# sch.net
KiCad netlist of a schematic drawn in EAGLE
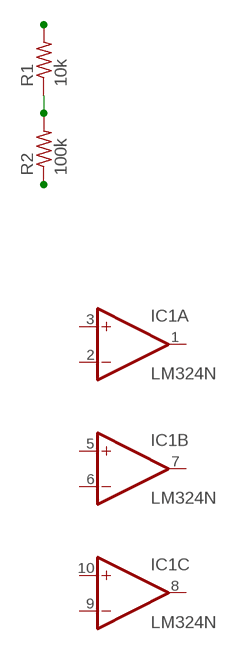
[diagram p0: schematic, sheet 1]

(export (version "E")
  (design (tool "Eeschema 10.0.6"))
  (components
    (comp (ref "IC1")
      (value "LM324N")
      (footprint "eagle-import:DIL14")
      (libsource (lib "eagle-import") (part "LM324N"))
    )
    (comp (ref "R1")
      (value "10k")
      (footprint "eagle-import:0204_7")
      (libsource (lib "eagle-import") (part "R-US_0204/7"))
    )
    (comp (ref "R2")
      (value "100k")
      (footprint "eagle-import:0204_7")
      (libsource (lib "eagle-import") (part "R-US_0204/7"))
    )
  )
  (nets
    (net (code "1") (name "Net-(R1-Pad1)") (class "Default")
      (node (ref "R1") (pin "1") (pinfunction "1_1") (pintype "passive"))
      (node (ref "R2") (pin "2") (pinfunction "2_2") (pintype "passive"))
    )
    (net (code "2") (name "unconnected-(IC1A-+IN-Pad3)") (class "Default")
      (node (ref "IC1") (pin "3") (pinfunction "+IN_3") (pintype "input"))
    )
    (net (code "3") (name "unconnected-(IC1A--IN-Pad2)") (class "Default")
      (node (ref "IC1") (pin "2") (pinfunction "-IN_2") (pintype "input"))
    )
    (net (code "4") (name "unconnected-(IC1A-OUT-Pad1)") (class "Default")
      (node (ref "IC1") (pin "1") (pinfunction "OUT_1") (pintype "output"))
    )
    (net (code "5") (name "unconnected-(IC1B-+IN-Pad5)") (class "Default")
      (node (ref "IC1") (pin "5") (pinfunction "+IN_5") (pintype "input"))
    )
    (net (code "6") (name "unconnected-(IC1B--IN-Pad6)") (class "Default")
      (node (ref "IC1") (pin "6") (pinfunction "-IN_6") (pintype "input"))
    )
    (net (code "7") (name "unconnected-(IC1B-OUT-Pad7)") (class "Default")
      (node (ref "IC1") (pin "7") (pinfunction "OUT_7") (pintype "output"))
    )
    (net (code "8") (name "unconnected-(IC1C-+IN-Pad10)") (class "Default")
      (node (ref "IC1") (pin "10") (pinfunction "+IN_10") (pintype "input"))
    )
    (net (code "9") (name "unconnected-(IC1C--IN-Pad9)") (class "Default")
      (node (ref "IC1") (pin "9") (pinfunction "-IN_9") (pintype "input"))
    )
    (net (code "10") (name "unconnected-(IC1C-OUT-Pad8)") (class "Default")
      (node (ref "IC1") (pin "8") (pinfunction "OUT_8") (pintype "output"))
    )
    (net (code "11") (name "unconnected-(R1-Pad2)") (class "Default")
      (node (ref "R1") (pin "2") (pinfunction "2_2") (pintype "passive"))
    )
    (net (code "12") (name "unconnected-(R2-Pad1)") (class "Default")
      (node (ref "R2") (pin "1") (pinfunction "1_1") (pintype "passive"))
    )
  )
)
